# SCH_555_Timer_Based_Keyboard_2023-12-17.net
KiCad netlist of a schematic drawn in EasyEDA
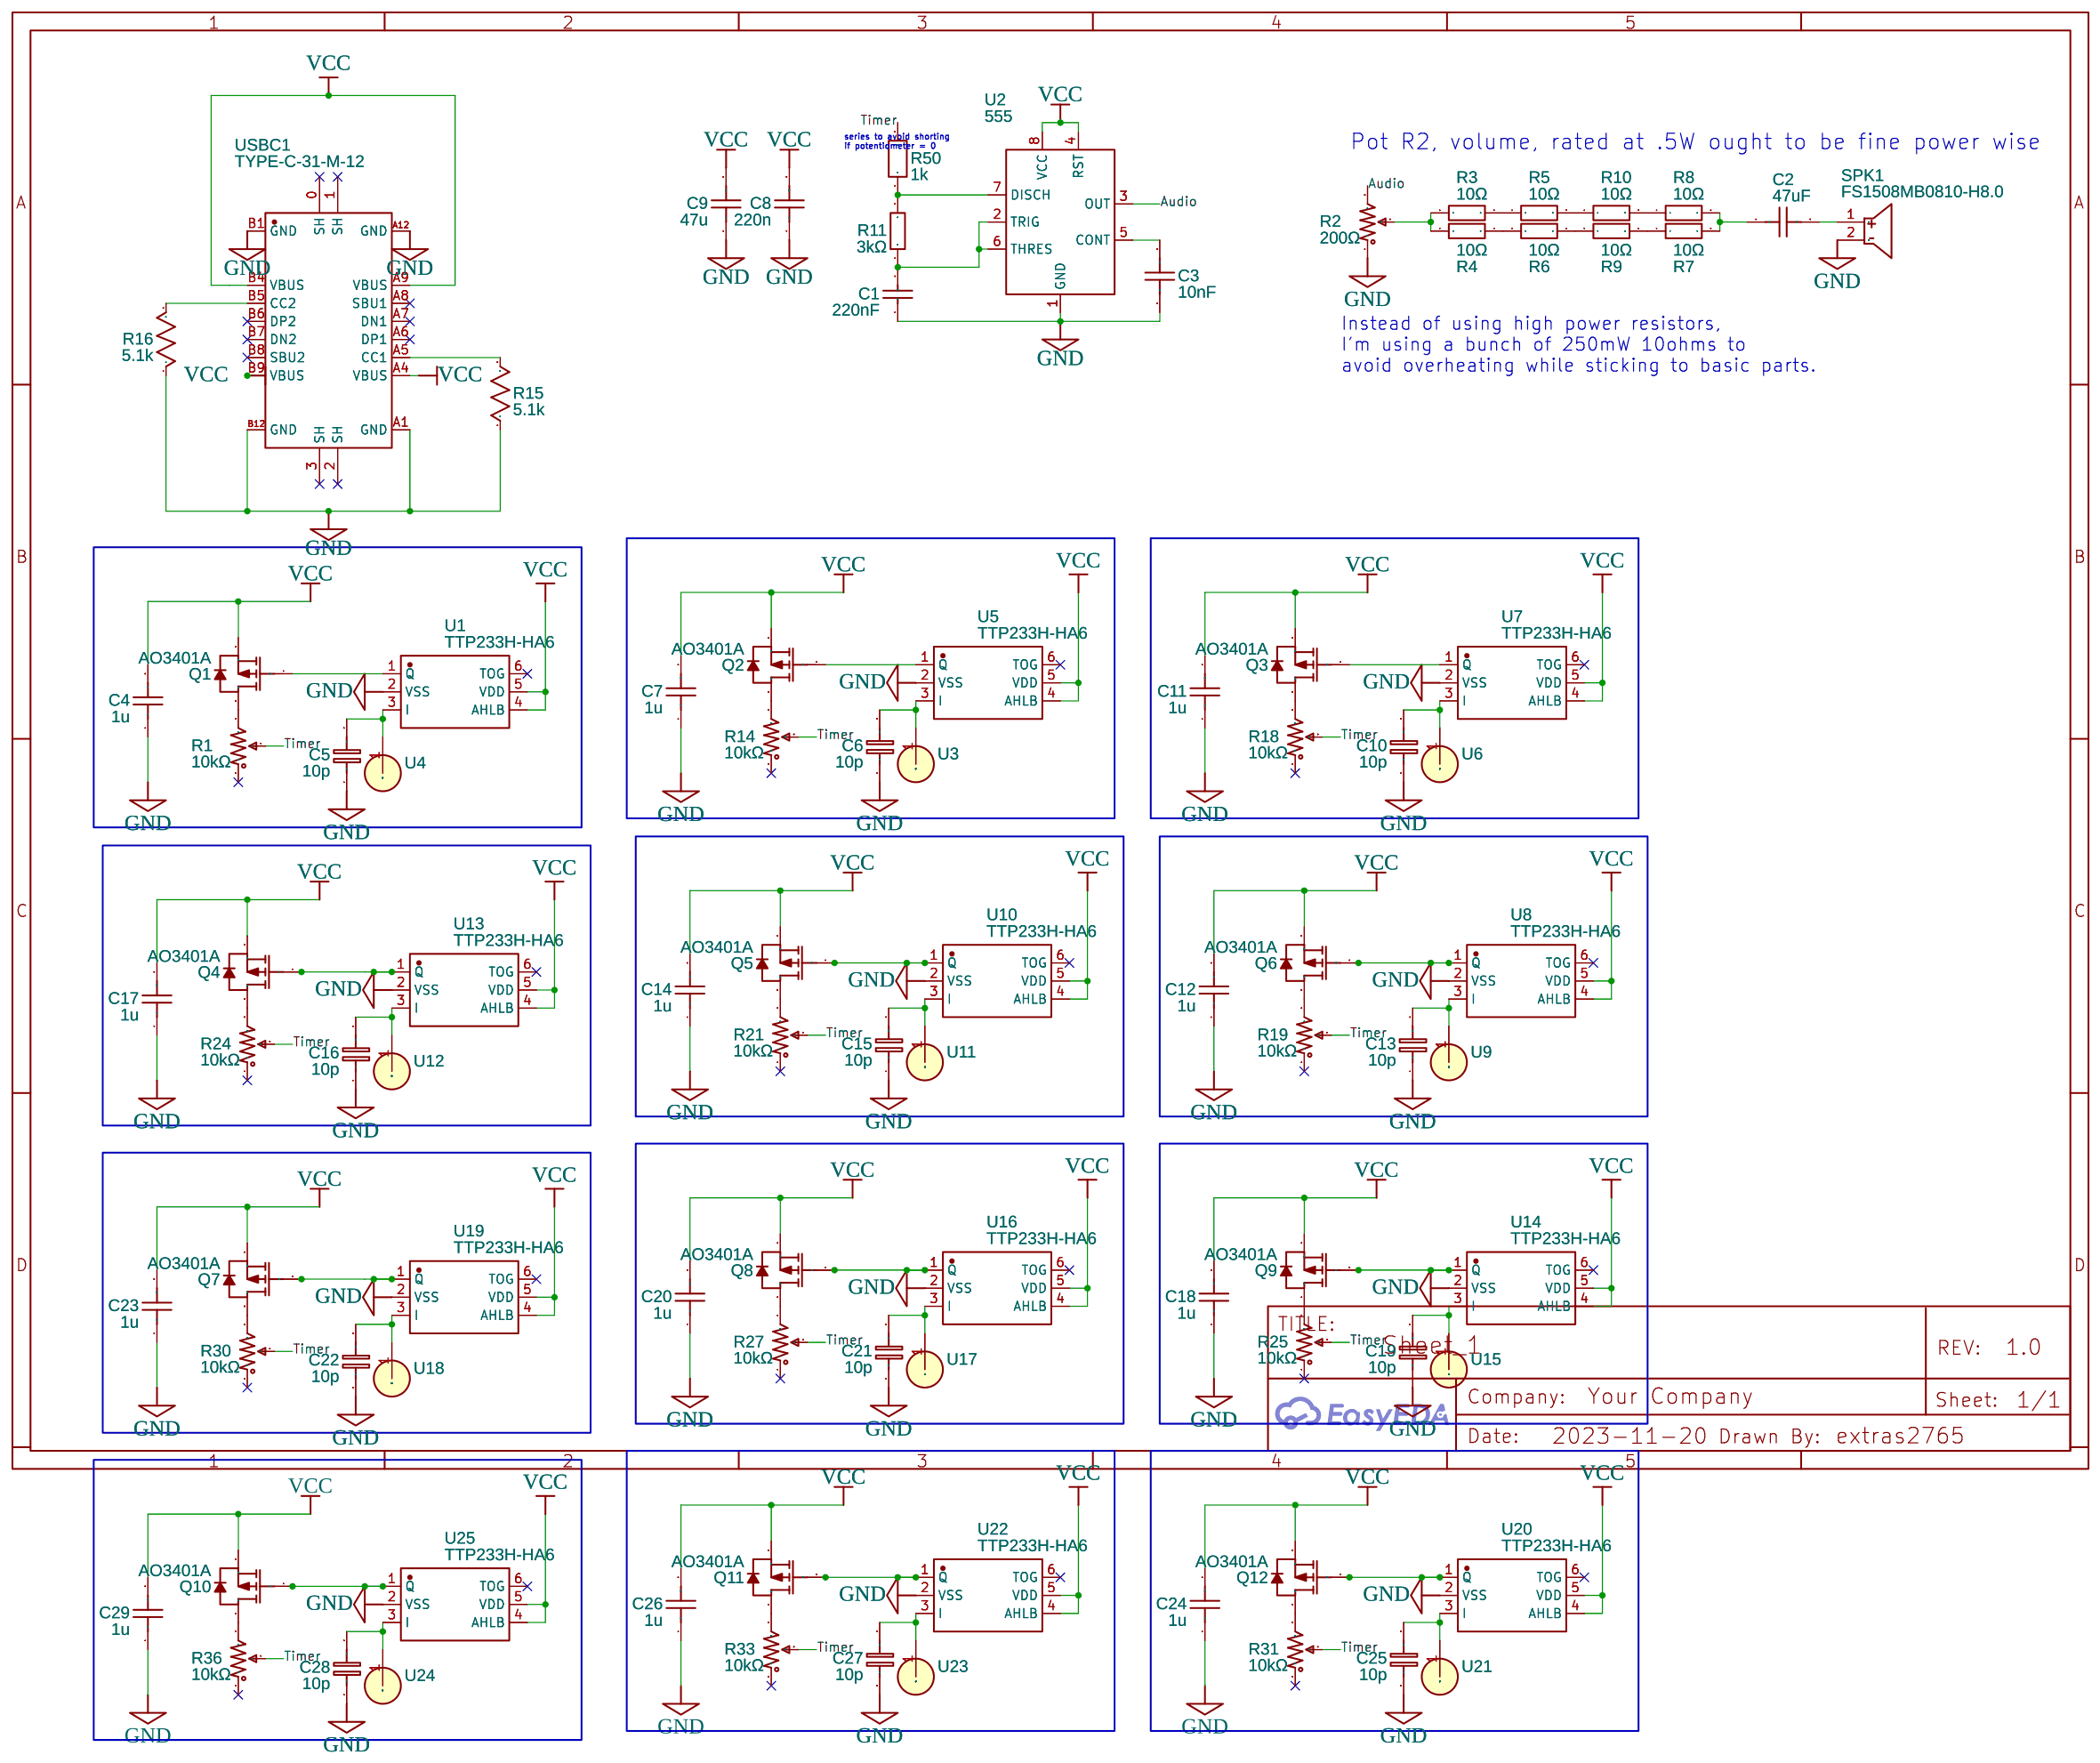
[diagram p0: schematic sheet]

(export (version "E")
  (design (tool "Eeschema 10.0.6"))
  (components
    (comp (ref "C1")
      (value "220nF")
      (fields
        (field (name "Manufacturer Part") "CL21B224KBFNNNE")
        (field (name "Manufacturer") "SAMSUNG(三星)")
      )
      (libsource (lib "") (part "CL21B224KBFNNNE"))
    )
    (comp (ref "C2")
      (value "47uF")
      (fields
        (field (name "Manufacturer Part") "CL31A476MPHNNNE")
        (field (name "Manufacturer") "SAMSUNG(三星)")
      )
      (libsource (lib "") (part "CL31A476MPHNNNE"))
    )
    (comp (ref "C3") (value "10nF") (libsource (lib "") (part "C_0805_US")))
    (comp (ref "C4") (value "1u") (libsource (lib "") (part "C_0805_US_1")))
    (comp (ref "C5") (value "10p") (libsource (lib "") (part "C_0603_EU_1")))
    (comp (ref "C6") (value "10p") (libsource (lib "") (part "C_0603_EU_1")))
    (comp (ref "C7") (value "1u") (libsource (lib "") (part "C_0805_US_1")))
    (comp (ref "C8") (value "220n") (libsource (lib "") (part "C_0805_US_1")))
    (comp (ref "C9") (value "47u") (libsource (lib "") (part "C_0805_US_1")))
    (comp (ref "C10") (value "10p") (libsource (lib "") (part "C_0603_EU_2")))
    (comp (ref "C11") (value "1u") (libsource (lib "") (part "C_0805_US_1")))
    (comp (ref "C12") (value "1u") (libsource (lib "") (part "C_0805_US_1")))
    (comp (ref "C13") (value "10p") (libsource (lib "") (part "C_0603_EU_2")))
    (comp (ref "C14") (value "1u") (libsource (lib "") (part "C_0805_US_1")))
    (comp (ref "C15") (value "10p") (libsource (lib "") (part "C_0603_EU_1")))
    (comp (ref "C16") (value "10p") (libsource (lib "") (part "C_0603_EU_1")))
    (comp (ref "C17") (value "1u") (libsource (lib "") (part "C_0805_US_1")))
    (comp (ref "C18") (value "1u") (libsource (lib "") (part "C_0805_US_1")))
    (comp (ref "C19") (value "10p") (libsource (lib "") (part "C_0603_EU_3")))
    (comp (ref "C20") (value "1u") (libsource (lib "") (part "C_0805_US_1")))
    (comp (ref "C21") (value "10p") (libsource (lib "") (part "C_0603_EU")))
    (comp (ref "C22") (value "10p") (libsource (lib "") (part "C_0603_EU")))
    (comp (ref "C23") (value "1u") (libsource (lib "") (part "C_0805_US_1")))
    (comp (ref "C24") (value "1u") (libsource (lib "") (part "C_0805_US_1")))
    (comp (ref "C25") (value "10p") (libsource (lib "") (part "C_0603_EU_3")))
    (comp (ref "C26") (value "1u") (libsource (lib "") (part "C_0805_US_1")))
    (comp (ref "C27") (value "10p") (libsource (lib "") (part "C_0603_EU")))
    (comp (ref "C28") (value "10p") (libsource (lib "") (part "C_0603_EU")))
    (comp (ref "C29") (value "1u") (libsource (lib "") (part "C_0805_US_1")))
    (comp (ref "Q1")
      (value "AO3401A")
      (fields (field (name "Manufacturer") "AOS"))
      (libsource (lib "") (part "AO3401A"))
    )
    (comp (ref "Q2")
      (value "AO3401A")
      (fields (field (name "Manufacturer") "AOS"))
      (libsource (lib "") (part "AO3401A"))
    )
    (comp (ref "Q3")
      (value "AO3401A")
      (fields (field (name "Manufacturer") "AOS"))
      (libsource (lib "") (part "AO3401A"))
    )
    (comp (ref "Q4")
      (value "AO3401A")
      (fields (field (name "Manufacturer") "AOS"))
      (libsource (lib "") (part "AO3401A"))
    )
    (comp (ref "Q5")
      (value "AO3401A")
      (fields (field (name "Manufacturer") "AOS"))
      (libsource (lib "") (part "AO3401A"))
    )
    (comp (ref "Q6")
      (value "AO3401A")
      (fields (field (name "Manufacturer") "AOS"))
      (libsource (lib "") (part "AO3401A"))
    )
    (comp (ref "Q7")
      (value "AO3401A")
      (fields (field (name "Manufacturer") "AOS"))
      (libsource (lib "") (part "AO3401A"))
    )
    (comp (ref "Q8")
      (value "AO3401A")
      (fields (field (name "Manufacturer") "AOS"))
      (libsource (lib "") (part "AO3401A"))
    )
    (comp (ref "Q9")
      (value "AO3401A")
      (fields (field (name "Manufacturer") "AOS"))
      (libsource (lib "") (part "AO3401A"))
    )
    (comp (ref "Q10")
      (value "AO3401A")
      (fields (field (name "Manufacturer") "AOS"))
      (libsource (lib "") (part "AO3401A"))
    )
    (comp (ref "Q11")
      (value "AO3401A")
      (fields (field (name "Manufacturer") "AOS"))
      (libsource (lib "") (part "AO3401A"))
    )
    (comp (ref "Q12")
      (value "AO3401A")
      (fields (field (name "Manufacturer") "AOS"))
      (libsource (lib "") (part "AO3401A"))
    )
    (comp (ref "R1")
      (value "10kΩ")
      (fields (field (name "Manufacturer Part") "3296W-1-103") (field (name "Manufacturer") "BOCHEN(博晨)"))
      (libsource (lib "") (part "3296W-1-103"))
    )
    (comp (ref "R2")
      (value "200Ω")
      (fields (field (name "Manufacturer Part") "3386P-1-201TLF") (field (name "Manufacturer") "BOURNS"))
      (libsource (lib "") (part "3386P-1-201TLF"))
    )
    (comp (ref "R3")
      (value "10Ω")
      (fields
        (field (name "Manufacturer Part") "1206W4F100JT5E")
        (field (name "Manufacturer") "UNI-ROYAL(厚声)")
      )
      (libsource (lib "") (part "1206W4F100JT5E"))
    )
    (comp (ref "R4")
      (value "10Ω")
      (fields
        (field (name "Manufacturer Part") "1206W4F100JT5E")
        (field (name "Manufacturer") "UNI-ROYAL(厚声)")
      )
      (libsource (lib "") (part "1206W4F100JT5E"))
    )
    (comp (ref "R5")
      (value "10Ω")
      (fields
        (field (name "Manufacturer Part") "1206W4F100JT5E")
        (field (name "Manufacturer") "UNI-ROYAL(厚声)")
      )
      (libsource (lib "") (part "1206W4F100JT5E"))
    )
    (comp (ref "R6")
      (value "10Ω")
      (fields
        (field (name "Manufacturer Part") "1206W4F100JT5E")
        (field (name "Manufacturer") "UNI-ROYAL(厚声)")
      )
      (libsource (lib "") (part "1206W4F100JT5E"))
    )
    (comp (ref "R7")
      (value "10Ω")
      (fields
        (field (name "Manufacturer Part") "1206W4F100JT5E")
        (field (name "Manufacturer") "UNI-ROYAL(厚声)")
      )
      (libsource (lib "") (part "1206W4F100JT5E"))
    )
    (comp (ref "R8")
      (value "10Ω")
      (fields
        (field (name "Manufacturer Part") "1206W4F100JT5E")
        (field (name "Manufacturer") "UNI-ROYAL(厚声)")
      )
      (libsource (lib "") (part "1206W4F100JT5E"))
    )
    (comp (ref "R9")
      (value "10Ω")
      (fields
        (field (name "Manufacturer Part") "1206W4F100JT5E")
        (field (name "Manufacturer") "UNI-ROYAL(厚声)")
      )
      (libsource (lib "") (part "1206W4F100JT5E"))
    )
    (comp (ref "R10")
      (value "10Ω")
      (fields
        (field (name "Manufacturer Part") "1206W4F100JT5E")
        (field (name "Manufacturer") "UNI-ROYAL(厚声)")
      )
      (libsource (lib "") (part "1206W4F100JT5E"))
    )
    (comp (ref "R11")
      (value "3kΩ")
      (fields
        (field (name "Manufacturer Part") "0805W8F3001T5E")
        (field (name "Manufacturer") "UNI-ROYAL(厚声)")
      )
      (libsource (lib "") (part "0805W8F3001T5E"))
    )
    (comp (ref "R14")
      (value "10kΩ")
      (fields (field (name "Manufacturer Part") "3296W-1-103") (field (name "Manufacturer") "BOCHEN(博晨)"))
      (libsource (lib "") (part "3296W-1-103"))
    )
    (comp (ref "R15") (value "5.1k") (libsource (lib "") (part "R_0805_US_1")))
    (comp (ref "R16") (value "5.1k") (libsource (lib "") (part "R_0805_US")))
    (comp (ref "R18")
      (value "10kΩ")
      (fields (field (name "Manufacturer Part") "3296W-1-103") (field (name "Manufacturer") "BOCHEN(博晨)"))
      (libsource (lib "") (part "3296W-1-103"))
    )
    (comp (ref "R19")
      (value "10kΩ")
      (fields (field (name "Manufacturer Part") "3296W-1-103") (field (name "Manufacturer") "BOCHEN(博晨)"))
      (libsource (lib "") (part "3296W-1-103"))
    )
    (comp (ref "R21")
      (value "10kΩ")
      (fields (field (name "Manufacturer Part") "3296W-1-103") (field (name "Manufacturer") "BOCHEN(博晨)"))
      (libsource (lib "") (part "3296W-1-103"))
    )
    (comp (ref "R24")
      (value "10kΩ")
      (fields (field (name "Manufacturer Part") "3296W-1-103") (field (name "Manufacturer") "BOCHEN(博晨)"))
      (libsource (lib "") (part "3296W-1-103"))
    )
    (comp (ref "R25")
      (value "10kΩ")
      (fields (field (name "Manufacturer Part") "3296W-1-103") (field (name "Manufacturer") "BOCHEN(博晨)"))
      (libsource (lib "") (part "3296W-1-103"))
    )
    (comp (ref "R27")
      (value "10kΩ")
      (fields (field (name "Manufacturer Part") "3296W-1-103") (field (name "Manufacturer") "BOCHEN(博晨)"))
      (libsource (lib "") (part "3296W-1-103"))
    )
    (comp (ref "R30")
      (value "10kΩ")
      (fields (field (name "Manufacturer Part") "3296W-1-103") (field (name "Manufacturer") "BOCHEN(博晨)"))
      (libsource (lib "") (part "3296W-1-103"))
    )
    (comp (ref "R31")
      (value "10kΩ")
      (fields (field (name "Manufacturer Part") "3296W-1-103") (field (name "Manufacturer") "BOCHEN(博晨)"))
      (libsource (lib "") (part "3296W-1-103"))
    )
    (comp (ref "R33")
      (value "10kΩ")
      (fields (field (name "Manufacturer Part") "3296W-1-103") (field (name "Manufacturer") "BOCHEN(博晨)"))
      (libsource (lib "") (part "3296W-1-103"))
    )
    (comp (ref "R36")
      (value "10kΩ")
      (fields (field (name "Manufacturer Part") "3296W-1-103") (field (name "Manufacturer") "BOCHEN(博晨)"))
      (libsource (lib "") (part "3296W-1-103"))
    )
    (comp (ref "R50") (value "1k") (libsource (lib "") (part "R_0805_EU")))
    (comp (ref "SPK1")
      (value "FS1508MB0810-H8.0")
      (fields (field (name "Manufacturer") "FUET(福声科技)"))
      (libsource (lib "") (part "FS1508MB0810-H8.0"))
    )
    (comp (ref "U1")
      (value "TTP233H-HA6")
      (fields (field (name "Manufacturer") "TONTEK(通泰)"))
      (libsource (lib "") (part "TTP233H-HA6"))
    )
    (comp (ref "U2")
      (value "555")
      (fields (field (name "Manufacturer Part") "NE555DR") (field (name "Manufacturer") "TI(德州仪器)"))
      (libsource (lib "") (part "NE555DR"))
    )
    (comp (ref "U3") (value "TouchPad") (libsource (lib "") (part "TouchPad")))
    (comp (ref "U4") (value "TouchPad") (libsource (lib "") (part "TouchPad")))
    (comp (ref "U5")
      (value "TTP233H-HA6")
      (fields (field (name "Manufacturer") "TONTEK(通泰)"))
      (libsource (lib "") (part "TTP233H-HA6"))
    )
    (comp (ref "U6") (value "TouchPad") (libsource (lib "") (part "TouchPad")))
    (comp (ref "U7")
      (value "TTP233H-HA6")
      (fields (field (name "Manufacturer") "TONTEK(通泰)"))
      (libsource (lib "") (part "TTP233H-HA6"))
    )
    (comp (ref "U8")
      (value "TTP233H-HA6")
      (fields (field (name "Manufacturer") "TONTEK(通泰)"))
      (libsource (lib "") (part "TTP233H-HA6"))
    )
    (comp (ref "U9") (value "TouchPad") (libsource (lib "") (part "TouchPad")))
    (comp (ref "U10")
      (value "TTP233H-HA6")
      (fields (field (name "Manufacturer") "TONTEK(通泰)"))
      (libsource (lib "") (part "TTP233H-HA6"))
    )
    (comp (ref "U11") (value "TouchPad") (libsource (lib "") (part "TouchPad")))
    (comp (ref "U12") (value "TouchPad") (libsource (lib "") (part "TouchPad")))
    (comp (ref "U13")
      (value "TTP233H-HA6")
      (fields (field (name "Manufacturer") "TONTEK(通泰)"))
      (libsource (lib "") (part "TTP233H-HA6"))
    )
    (comp (ref "U14")
      (value "TTP233H-HA6")
      (fields (field (name "Manufacturer") "TONTEK(通泰)"))
      (libsource (lib "") (part "TTP233H-HA6"))
    )
    (comp (ref "U15") (value "TouchPad") (libsource (lib "") (part "TouchPad")))
    (comp (ref "U16")
      (value "TTP233H-HA6")
      (fields (field (name "Manufacturer") "TONTEK(通泰)"))
      (libsource (lib "") (part "TTP233H-HA6"))
    )
    (comp (ref "U17") (value "TouchPad") (libsource (lib "") (part "TouchPad")))
    (comp (ref "U18") (value "TouchPad") (libsource (lib "") (part "TouchPad")))
    (comp (ref "U19")
      (value "TTP233H-HA6")
      (fields (field (name "Manufacturer") "TONTEK(通泰)"))
      (libsource (lib "") (part "TTP233H-HA6"))
    )
    (comp (ref "U20")
      (value "TTP233H-HA6")
      (fields (field (name "Manufacturer") "TONTEK(通泰)"))
      (libsource (lib "") (part "TTP233H-HA6"))
    )
    (comp (ref "U21") (value "TouchPad") (libsource (lib "") (part "TouchPad")))
    (comp (ref "U22")
      (value "TTP233H-HA6")
      (fields (field (name "Manufacturer") "TONTEK(通泰)"))
      (libsource (lib "") (part "TTP233H-HA6"))
    )
    (comp (ref "U23") (value "TouchPad") (libsource (lib "") (part "TouchPad")))
    (comp (ref "U24") (value "TouchPad") (libsource (lib "") (part "TouchPad")))
    (comp (ref "U25")
      (value "TTP233H-HA6")
      (fields (field (name "Manufacturer") "TONTEK(通泰)"))
      (libsource (lib "") (part "TTP233H-HA6"))
    )
    (comp (ref "USBC1")
      (value "TYPE-C-31-M-12")
      (fields (field (name "Manufacturer") "韩国韩荣"))
      (libsource (lib "") (part "TYPE-C-31-M-12"))
    )
  )
  (nets
    (net (code "1") (name "/Audio") (class "Default")
      (node (ref "R2") (pin "3") (pinfunction "3_3") (pintype "unspecified"))
      (node (ref "U2") (pin "3") (pinfunction "OUT_3") (pintype "unspecified"))
    )
    (net (code "2") (name "/Timer") (class "Default")
      (node (ref "R1") (pin "2") (pinfunction "2_2") (pintype "unspecified"))
      (node (ref "R14") (pin "2") (pinfunction "2_2") (pintype "unspecified"))
      (node (ref "R18") (pin "2") (pinfunction "2_2") (pintype "unspecified"))
      (node (ref "R19") (pin "2") (pinfunction "2_2") (pintype "unspecified"))
      (node (ref "R21") (pin "2") (pinfunction "2_2") (pintype "unspecified"))
      (node (ref "R24") (pin "2") (pinfunction "2_2") (pintype "unspecified"))
      (node (ref "R25") (pin "2") (pinfunction "2_2") (pintype "unspecified"))
      (node (ref "R27") (pin "2") (pinfunction "2_2") (pintype "unspecified"))
      (node (ref "R30") (pin "2") (pinfunction "2_2") (pintype "unspecified"))
      (node (ref "R31") (pin "2") (pinfunction "2_2") (pintype "unspecified"))
      (node (ref "R33") (pin "2") (pinfunction "2_2") (pintype "unspecified"))
      (node (ref "R36") (pin "2") (pinfunction "2_2") (pintype "unspecified"))
      (node (ref "R50") (pin "2") (pinfunction "2_2") (pintype "unspecified"))
    )
    (net (code "3") (name "GND") (class "Default")
      (node (ref "C1") (pin "1") (pinfunction "1_1") (pintype "input"))
      (node (ref "C10") (pin "1") (pinfunction "1_1") (pintype "unspecified"))
      (node (ref "C11") (pin "1") (pinfunction "1_1") (pintype "unspecified"))
      (node (ref "C12") (pin "1") (pinfunction "1_1") (pintype "unspecified"))
      (node (ref "C13") (pin "1") (pinfunction "1_1") (pintype "unspecified"))
      (node (ref "C14") (pin "1") (pinfunction "1_1") (pintype "unspecified"))
      (node (ref "C15") (pin "1") (pinfunction "1_1") (pintype "unspecified"))
      (node (ref "C16") (pin "1") (pinfunction "1_1") (pintype "unspecified"))
      (node (ref "C17") (pin "1") (pinfunction "1_1") (pintype "unspecified"))
      (node (ref "C18") (pin "1") (pinfunction "1_1") (pintype "unspecified"))
      (node (ref "C19") (pin "1") (pinfunction "1_1") (pintype "unspecified"))
      (node (ref "C20") (pin "1") (pinfunction "1_1") (pintype "unspecified"))
      (node (ref "C21") (pin "1") (pinfunction "1_1") (pintype "unspecified"))
      (node (ref "C22") (pin "1") (pinfunction "1_1") (pintype "unspecified"))
      (node (ref "C23") (pin "1") (pinfunction "1_1") (pintype "unspecified"))
      (node (ref "C24") (pin "1") (pinfunction "1_1") (pintype "unspecified"))
      (node (ref "C25") (pin "1") (pinfunction "1_1") (pintype "unspecified"))
      (node (ref "C26") (pin "1") (pinfunction "1_1") (pintype "unspecified"))
      (node (ref "C27") (pin "1") (pinfunction "1_1") (pintype "unspecified"))
      (node (ref "C28") (pin "1") (pinfunction "1_1") (pintype "unspecified"))
      (node (ref "C29") (pin "1") (pinfunction "1_1") (pintype "unspecified"))
      (node (ref "C3") (pin "1") (pinfunction "1_1") (pintype "unspecified"))
      (node (ref "C4") (pin "1") (pinfunction "1_1") (pintype "unspecified"))
      (node (ref "C5") (pin "1") (pinfunction "1_1") (pintype "unspecified"))
      (node (ref "C6") (pin "1") (pinfunction "1_1") (pintype "unspecified"))
      (node (ref "C7") (pin "1") (pinfunction "1_1") (pintype "unspecified"))
      (node (ref "C8") (pin "1") (pinfunction "1_1") (pintype "unspecified"))
      (node (ref "C9") (pin "1") (pinfunction "1_1") (pintype "unspecified"))
      (node (ref "R15") (pin "1") (pinfunction "1_1") (pintype "unspecified"))
      (node (ref "R16") (pin "1") (pinfunction "1_1") (pintype "unspecified"))
      (node (ref "R2") (pin "1") (pinfunction "1_1") (pintype "unspecified"))
      (node (ref "SPK1") (pin "2") (pinfunction "2_2") (pintype "unspecified"))
      (node (ref "U1") (pin "2") (pinfunction "VSS_2") (pintype "unspecified"))
      (node (ref "U10") (pin "2") (pinfunction "VSS_2") (pintype "unspecified"))
      (node (ref "U13") (pin "2") (pinfunction "VSS_2") (pintype "unspecified"))
      (node (ref "U14") (pin "2") (pinfunction "VSS_2") (pintype "unspecified"))
      (node (ref "U16") (pin "2") (pinfunction "VSS_2") (pintype "unspecified"))
      (node (ref "U19") (pin "2") (pinfunction "VSS_2") (pintype "unspecified"))
      (node (ref "U2") (pin "1") (pinfunction "GND_1") (pintype "unspecified"))
      (node (ref "U20") (pin "2") (pinfunction "VSS_2") (pintype "unspecified"))
      (node (ref "U22") (pin "2") (pinfunction "VSS_2") (pintype "unspecified"))
      (node (ref "U25") (pin "2") (pinfunction "VSS_2") (pintype "unspecified"))
      (node (ref "U5") (pin "2") (pinfunction "VSS_2") (pintype "unspecified"))
      (node (ref "U7") (pin "2") (pinfunction "VSS_2") (pintype "unspecified"))
      (node (ref "U8") (pin "2") (pinfunction "VSS_2") (pintype "unspecified"))
      (node (ref "USBC1") (pin "A1") (pinfunction "GND_A1") (pintype "unspecified"))
      (node (ref "USBC1") (pin "A12") (pinfunction "GND_A12") (pintype "unspecified"))
      (node (ref "USBC1") (pin "B1") (pinfunction "GND_B1") (pintype "unspecified"))
      (node (ref "USBC1") (pin "B12") (pinfunction "GND_B12") (pintype "unspecified"))
    )
    (net (code "4") (name "Net-(C2-Pad1)") (class "Default")
      (node (ref "C2") (pin "1") (pinfunction "1_1") (pintype "unspecified"))
      (node (ref "R7") (pin "2") (pinfunction "2_2") (pintype "input"))
      (node (ref "R8") (pin "2") (pinfunction "2_2") (pintype "input"))
    )
    (net (code "5") (name "Net-(C2-Pad2)") (class "Default")
      (node (ref "C2") (pin "2") (pinfunction "2_2") (pintype "unspecified"))
      (node (ref "SPK1") (pin "1") (pinfunction "1_1") (pintype "unspecified"))
    )
    (net (code "6") (name "Net-(Q1-D)") (class "Default")
      (node (ref "Q1") (pin "3") (pinfunction "D_3") (pintype "unspecified"))
      (node (ref "R1") (pin "3") (pinfunction "3_3") (pintype "unspecified"))
    )
    (net (code "7") (name "Net-(Q1-G)") (class "Default")
      (node (ref "Q1") (pin "1") (pinfunction "G_1") (pintype "unspecified"))
      (node (ref "U1") (pin "1") (pinfunction "Q_1") (pintype "unspecified"))
    )
    (net (code "8") (name "Net-(Q2-D)") (class "Default")
      (node (ref "Q2") (pin "3") (pinfunction "D_3") (pintype "unspecified"))
      (node (ref "R14") (pin "3") (pinfunction "3_3") (pintype "unspecified"))
    )
    (net (code "9") (name "Net-(Q2-G)") (class "Default")
      (node (ref "Q2") (pin "1") (pinfunction "G_1") (pintype "unspecified"))
      (node (ref "U5") (pin "1") (pinfunction "Q_1") (pintype "unspecified"))
    )
    (net (code "10") (name "Net-(Q3-D)") (class "Default")
      (node (ref "Q3") (pin "3") (pinfunction "D_3") (pintype "unspecified"))
      (node (ref "R18") (pin "3") (pinfunction "3_3") (pintype "unspecified"))
    )
    (net (code "11") (name "Net-(Q3-G)") (class "Default")
      (node (ref "Q3") (pin "1") (pinfunction "G_1") (pintype "unspecified"))
      (node (ref "U7") (pin "1") (pinfunction "Q_1") (pintype "unspecified"))
    )
    (net (code "12") (name "Net-(Q4-D)") (class "Default")
      (node (ref "Q4") (pin "3") (pinfunction "D_3") (pintype "unspecified"))
      (node (ref "R24") (pin "3") (pinfunction "3_3") (pintype "unspecified"))
    )
    (net (code "13") (name "Net-(Q4-G)") (class "Default")
      (node (ref "Q4") (pin "1") (pinfunction "G_1") (pintype "unspecified"))
      (node (ref "U13") (pin "1") (pinfunction "Q_1") (pintype "unspecified"))
    )
    (net (code "14") (name "Net-(Q5-D)") (class "Default")
      (node (ref "Q5") (pin "3") (pinfunction "D_3") (pintype "unspecified"))
      (node (ref "R21") (pin "3") (pinfunction "3_3") (pintype "unspecified"))
    )
    (net (code "15") (name "Net-(Q5-G)") (class "Default")
      (node (ref "Q5") (pin "1") (pinfunction "G_1") (pintype "unspecified"))
      (node (ref "U10") (pin "1") (pinfunction "Q_1") (pintype "unspecified"))
    )
    (net (code "16") (name "Net-(Q6-D)") (class "Default")
      (node (ref "Q6") (pin "3") (pinfunction "D_3") (pintype "unspecified"))
      (node (ref "R19") (pin "3") (pinfunction "3_3") (pintype "unspecified"))
    )
    (net (code "17") (name "Net-(Q6-G)") (class "Default")
      (node (ref "Q6") (pin "1") (pinfunction "G_1") (pintype "unspecified"))
      (node (ref "U8") (pin "1") (pinfunction "Q_1") (pintype "unspecified"))
    )
    (net (code "18") (name "Net-(Q7-D)") (class "Default")
      (node (ref "Q7") (pin "3") (pinfunction "D_3") (pintype "unspecified"))
      (node (ref "R30") (pin "3") (pinfunction "3_3") (pintype "unspecified"))
    )
    (net (code "19") (name "Net-(Q7-G)") (class "Default")
      (node (ref "Q7") (pin "1") (pinfunction "G_1") (pintype "unspecified"))
      (node (ref "U19") (pin "1") (pinfunction "Q_1") (pintype "unspecified"))
    )
    (net (code "20") (name "Net-(Q8-D)") (class "Default")
      (node (ref "Q8") (pin "3") (pinfunction "D_3") (pintype "unspecified"))
      (node (ref "R27") (pin "3") (pinfunction "3_3") (pintype "unspecified"))
    )
    (net (code "21") (name "Net-(Q8-G)") (class "Default")
      (node (ref "Q8") (pin "1") (pinfunction "G_1") (pintype "unspecified"))
      (node (ref "U16") (pin "1") (pinfunction "Q_1") (pintype "unspecified"))
    )
    (net (code "22") (name "Net-(Q9-D)") (class "Default")
      (node (ref "Q9") (pin "3") (pinfunction "D_3") (pintype "unspecified"))
      (node (ref "R25") (pin "3") (pinfunction "3_3") (pintype "unspecified"))
    )
    (net (code "23") (name "Net-(Q9-G)") (class "Default")
      (node (ref "Q9") (pin "1") (pinfunction "G_1") (pintype "unspecified"))
      (node (ref "U14") (pin "1") (pinfunction "Q_1") (pintype "unspecified"))
    )
    (net (code "24") (name "Net-(Q10-D)") (class "Default")
      (node (ref "Q10") (pin "3") (pinfunction "D_3") (pintype "unspecified"))
      (node (ref "R36") (pin "3") (pinfunction "3_3") (pintype "unspecified"))
    )
    (net (code "25") (name "Net-(Q10-G)") (class "Default")
      (node (ref "Q10") (pin "1") (pinfunction "G_1") (pintype "unspecified"))
      (node (ref "U25") (pin "1") (pinfunction "Q_1") (pintype "unspecified"))
    )
    (net (code "26") (name "Net-(Q11-D)") (class "Default")
      (node (ref "Q11") (pin "3") (pinfunction "D_3") (pintype "unspecified"))
      (node (ref "R33") (pin "3") (pinfunction "3_3") (pintype "unspecified"))
    )
    (net (code "27") (name "Net-(Q11-G)") (class "Default")
      (node (ref "Q11") (pin "1") (pinfunction "G_1") (pintype "unspecified"))
      (node (ref "U22") (pin "1") (pinfunction "Q_1") (pintype "unspecified"))
    )
    (net (code "28") (name "Net-(Q12-D)") (class "Default")
      (node (ref "Q12") (pin "3") (pinfunction "D_3") (pintype "unspecified"))
      (node (ref "R31") (pin "3") (pinfunction "3_3") (pintype "unspecified"))
    )
    (net (code "29") (name "Net-(Q12-G)") (class "Default")
      (node (ref "Q12") (pin "1") (pinfunction "G_1") (pintype "unspecified"))
      (node (ref "U20") (pin "1") (pinfunction "Q_1") (pintype "unspecified"))
    )
    (net (code "30") (name "Net-(R2-Pad2)") (class "Default")
      (node (ref "R2") (pin "2") (pinfunction "2_2") (pintype "unspecified"))
      (node (ref "R3") (pin "1") (pinfunction "1_1") (pintype "input"))
      (node (ref "R4") (pin "1") (pinfunction "1_1") (pintype "input"))
    )
    (net (code "31") (name "Net-(R3-Pad2)") (class "Default")
      (node (ref "R3") (pin "2") (pinfunction "2_2") (pintype "input"))
      (node (ref "R5") (pin "1") (pinfunction "1_1") (pintype "input"))
    )
    (net (code "32") (name "Net-(R4-Pad2)") (class "Default")
      (node (ref "R4") (pin "2") (pinfunction "2_2") (pintype "input"))
      (node (ref "R6") (pin "1") (pinfunction "1_1") (pintype "input"))
    )
    (net (code "33") (name "Net-(R6-Pad2)") (class "Default")
      (node (ref "R6") (pin "2") (pinfunction "2_2") (pintype "input"))
      (node (ref "R9") (pin "1") (pinfunction "1_1") (pintype "input"))
    )
    (net (code "34") (name "Net-(R7-Pad1)") (class "Default")
      (node (ref "R7") (pin "1") (pinfunction "1_1") (pintype "input"))
      (node (ref "R9") (pin "2") (pinfunction "2_2") (pintype "input"))
    )
    (net (code "35") (name "Net-(R10-Pad1)") (class "Default")
      (node (ref "R10") (pin "1") (pinfunction "1_1") (pintype "input"))
      (node (ref "R5") (pin "2") (pinfunction "2_2") (pintype "input"))
    )
    (net (code "36") (name "Net-(R10-Pad2)") (class "Default")
      (node (ref "R10") (pin "2") (pinfunction "2_2") (pintype "input"))
      (node (ref "R8") (pin "1") (pinfunction "1_1") (pintype "input"))
    )
    (net (code "37") (name "Net-(U1-I)") (class "Default")
      (node (ref "C5") (pin "2") (pinfunction "2_2") (pintype "unspecified"))
      (node (ref "U1") (pin "3") (pinfunction "I_3") (pintype "unspecified"))
      (node (ref "U4") (pin "1") (pinfunction "Touch_1") (pintype "unspecified"))
    )
    (net (code "38") (name "Net-(U2-CONT)") (class "Default")
      (node (ref "C3") (pin "2") (pinfunction "2_2") (pintype "unspecified"))
      (node (ref "U2") (pin "5") (pinfunction "CONT_5") (pintype "unspecified"))
    )
    (net (code "39") (name "Net-(U2-DISCH)") (class "Default")
      (node (ref "R11") (pin "2") (pinfunction "2_2") (pintype "input"))
      (node (ref "R50") (pin "1") (pinfunction "1_1") (pintype "unspecified"))
      (node (ref "U2") (pin "7") (pinfunction "DISCH_7") (pintype "unspecified"))
    )
    (net (code "40") (name "Net-(U2-THRES)") (class "Default")
      (node (ref "C1") (pin "2") (pinfunction "2_2") (pintype "input"))
      (node (ref "R11") (pin "1") (pinfunction "1_1") (pintype "input"))
      (node (ref "U2") (pin "2") (pinfunction "TRIG_2") (pintype "unspecified"))
      (node (ref "U2") (pin "6") (pinfunction "THRES_6") (pintype "unspecified"))
    )
    (net (code "41") (name "Net-(U3-Touch)") (class "Default")
      (node (ref "C6") (pin "2") (pinfunction "2_2") (pintype "unspecified"))
      (node (ref "U3") (pin "1") (pinfunction "Touch_1") (pintype "unspecified"))
      (node (ref "U5") (pin "3") (pinfunction "I_3") (pintype "unspecified"))
    )
    (net (code "42") (name "Net-(U6-Touch)") (class "Default")
      (node (ref "C10") (pin "2") (pinfunction "2_2") (pintype "unspecified"))
      (node (ref "U6") (pin "1") (pinfunction "Touch_1") (pintype "unspecified"))
      (node (ref "U7") (pin "3") (pinfunction "I_3") (pintype "unspecified"))
    )
    (net (code "43") (name "Net-(U8-I)") (class "Default")
      (node (ref "C13") (pin "2") (pinfunction "2_2") (pintype "unspecified"))
      (node (ref "U8") (pin "3") (pinfunction "I_3") (pintype "unspecified"))
      (node (ref "U9") (pin "1") (pinfunction "Touch_1") (pintype "unspecified"))
    )
    (net (code "44") (name "Net-(U10-I)") (class "Default")
      (node (ref "C15") (pin "2") (pinfunction "2_2") (pintype "unspecified"))
      (node (ref "U10") (pin "3") (pinfunction "I_3") (pintype "unspecified"))
      (node (ref "U11") (pin "1") (pinfunction "Touch_1") (pintype "unspecified"))
    )
    (net (code "45") (name "Net-(U12-Touch)") (class "Default")
      (node (ref "C16") (pin "2") (pinfunction "2_2") (pintype "unspecified"))
      (node (ref "U12") (pin "1") (pinfunction "Touch_1") (pintype "unspecified"))
      (node (ref "U13") (pin "3") (pinfunction "I_3") (pintype "unspecified"))
    )
    (net (code "46") (name "Net-(U14-I)") (class "Default")
      (node (ref "C19") (pin "2") (pinfunction "2_2") (pintype "unspecified"))
      (node (ref "U14") (pin "3") (pinfunction "I_3") (pintype "unspecified"))
      (node (ref "U15") (pin "1") (pinfunction "Touch_1") (pintype "unspecified"))
    )
    (net (code "47") (name "Net-(U16-I)") (class "Default")
      (node (ref "C21") (pin "2") (pinfunction "2_2") (pintype "unspecified"))
      (node (ref "U16") (pin "3") (pinfunction "I_3") (pintype "unspecified"))
      (node (ref "U17") (pin "1") (pinfunction "Touch_1") (pintype "unspecified"))
    )
    (net (code "48") (name "Net-(U18-Touch)") (class "Default")
      (node (ref "C22") (pin "2") (pinfunction "2_2") (pintype "unspecified"))
      (node (ref "U18") (pin "1") (pinfunction "Touch_1") (pintype "unspecified"))
      (node (ref "U19") (pin "3") (pinfunction "I_3") (pintype "unspecified"))
    )
    (net (code "49") (name "Net-(U20-I)") (class "Default")
      (node (ref "C25") (pin "2") (pinfunction "2_2") (pintype "unspecified"))
      (node (ref "U20") (pin "3") (pinfunction "I_3") (pintype "unspecified"))
      (node (ref "U21") (pin "1") (pinfunction "Touch_1") (pintype "unspecified"))
    )
    (net (code "50") (name "Net-(U22-I)") (class "Default")
      (node (ref "C27") (pin "2") (pinfunction "2_2") (pintype "unspecified"))
      (node (ref "U22") (pin "3") (pinfunction "I_3") (pintype "unspecified"))
      (node (ref "U23") (pin "1") (pinfunction "Touch_1") (pintype "unspecified"))
    )
    (net (code "51") (name "Net-(U24-Touch)") (class "Default")
      (node (ref "C28") (pin "2") (pinfunction "2_2") (pintype "unspecified"))
      (node (ref "U24") (pin "1") (pinfunction "Touch_1") (pintype "unspecified"))
      (node (ref "U25") (pin "3") (pinfunction "I_3") (pintype "unspecified"))
    )
    (net (code "52") (name "Net-(USBC1-CC1)") (class "Default")
      (node (ref "R15") (pin "2") (pinfunction "2_2") (pintype "unspecified"))
      (node (ref "USBC1") (pin "A5") (pinfunction "CC1_A5") (pintype "unspecified"))
    )
    (net (code "53") (name "Net-(USBC1-CC2)") (class "Default")
      (node (ref "R16") (pin "2") (pinfunction "2_2") (pintype "unspecified"))
      (node (ref "USBC1") (pin "B5") (pinfunction "CC2_B5") (pintype "unspecified"))
    )
    (net (code "54") (name "VCC") (class "Default")
      (node (ref "C11") (pin "2") (pinfunction "2_2") (pintype "unspecified"))
      (node (ref "C12") (pin "2") (pinfunction "2_2") (pintype "unspecified"))
      (node (ref "C14") (pin "2") (pinfunction "2_2") (pintype "unspecified"))
      (node (ref "C17") (pin "2") (pinfunction "2_2") (pintype "unspecified"))
      (node (ref "C18") (pin "2") (pinfunction "2_2") (pintype "unspecified"))
      (node (ref "C20") (pin "2") (pinfunction "2_2") (pintype "unspecified"))
      (node (ref "C23") (pin "2") (pinfunction "2_2") (pintype "unspecified"))
      (node (ref "C24") (pin "2") (pinfunction "2_2") (pintype "unspecified"))
      (node (ref "C26") (pin "2") (pinfunction "2_2") (pintype "unspecified"))
      (node (ref "C29") (pin "2") (pinfunction "2_2") (pintype "unspecified"))
      (node (ref "C4") (pin "2") (pinfunction "2_2") (pintype "unspecified"))
      (node (ref "C7") (pin "2") (pinfunction "2_2") (pintype "unspecified"))
      (node (ref "C8") (pin "2") (pinfunction "2_2") (pintype "unspecified"))
      (node (ref "C9") (pin "2") (pinfunction "2_2") (pintype "unspecified"))
      (node (ref "Q1") (pin "2") (pinfunction "S_2") (pintype "unspecified"))
      (node (ref "Q10") (pin "2") (pinfunction "S_2") (pintype "unspecified"))
      (node (ref "Q11") (pin "2") (pinfunction "S_2") (pintype "unspecified"))
      (node (ref "Q12") (pin "2") (pinfunction "S_2") (pintype "unspecified"))
      (node (ref "Q2") (pin "2") (pinfunction "S_2") (pintype "unspecified"))
      (node (ref "Q3") (pin "2") (pinfunction "S_2") (pintype "unspecified"))
      (node (ref "Q4") (pin "2") (pinfunction "S_2") (pintype "unspecified"))
      (node (ref "Q5") (pin "2") (pinfunction "S_2") (pintype "unspecified"))
      (node (ref "Q6") (pin "2") (pinfunction "S_2") (pintype "unspecified"))
      (node (ref "Q7") (pin "2") (pinfunction "S_2") (pintype "unspecified"))
      (node (ref "Q8") (pin "2") (pinfunction "S_2") (pintype "unspecified"))
      (node (ref "Q9") (pin "2") (pinfunction "S_2") (pintype "unspecified"))
      (node (ref "U1") (pin "4") (pinfunction "AHLB_4") (pintype "unspecified"))
      (node (ref "U1") (pin "5") (pinfunction "VDD_5") (pintype "unspecified"))
      (node (ref "U10") (pin "4") (pinfunction "AHLB_4") (pintype "unspecified"))
      (node (ref "U10") (pin "5") (pinfunction "VDD_5") (pintype "unspecified"))
      (node (ref "U13") (pin "4") (pinfunction "AHLB_4") (pintype "unspecified"))
      (node (ref "U13") (pin "5") (pinfunction "VDD_5") (pintype "unspecified"))
      (node (ref "U14") (pin "4") (pinfunction "AHLB_4") (pintype "unspecified"))
      (node (ref "U14") (pin "5") (pinfunction "VDD_5") (pintype "unspecified"))
      (node (ref "U16") (pin "4") (pinfunction "AHLB_4") (pintype "unspecified"))
      (node (ref "U16") (pin "5") (pinfunction "VDD_5") (pintype "unspecified"))
      (node (ref "U19") (pin "4") (pinfunction "AHLB_4") (pintype "unspecified"))
      (node (ref "U19") (pin "5") (pinfunction "VDD_5") (pintype "unspecified"))
      (node (ref "U2") (pin "4") (pinfunction "RST_4") (pintype "unspecified"))
      (node (ref "U2") (pin "8") (pinfunction "VCC_8") (pintype "unspecified"))
      (node (ref "U20") (pin "4") (pinfunction "AHLB_4") (pintype "unspecified"))
      (node (ref "U20") (pin "5") (pinfunction "VDD_5") (pintype "unspecified"))
      (node (ref "U22") (pin "4") (pinfunction "AHLB_4") (pintype "unspecified"))
      (node (ref "U22") (pin "5") (pinfunction "VDD_5") (pintype "unspecified"))
      (node (ref "U25") (pin "4") (pinfunction "AHLB_4") (pintype "unspecified"))
      (node (ref "U25") (pin "5") (pinfunction "VDD_5") (pintype "unspecified"))
      (node (ref "U5") (pin "4") (pinfunction "AHLB_4") (pintype "unspecified"))
      (node (ref "U5") (pin "5") (pinfunction "VDD_5") (pintype "unspecified"))
      (node (ref "U7") (pin "4") (pinfunction "AHLB_4") (pintype "unspecified"))
      (node (ref "U7") (pin "5") (pinfunction "VDD_5") (pintype "unspecified"))
      (node (ref "U8") (pin "4") (pinfunction "AHLB_4") (pintype "unspecified"))
      (node (ref "U8") (pin "5") (pinfunction "VDD_5") (pintype "unspecified"))
      (node (ref "USBC1") (pin "A4") (pinfunction "VBUS_A4") (pintype "unspecified"))
      (node (ref "USBC1") (pin "A9") (pinfunction "VBUS_A9") (pintype "unspecified"))
      (node (ref "USBC1") (pin "B4") (pinfunction "VBUS_B4") (pintype "unspecified"))
      (node (ref "USBC1") (pin "B9") (pinfunction "VBUS_B9") (pintype "unspecified"))
    )
    (net (code "55") (name "unconnected-(R1-Pad1)") (class "Default")
      (node (ref "R1") (pin "1") (pinfunction "1_1") (pintype "unspecified+no_connect"))
    )
    (net (code "56") (name "unconnected-(R14-Pad1)") (class "Default")
      (node (ref "R14") (pin "1") (pinfunction "1_1") (pintype "unspecified+no_connect"))
    )
    (net (code "57") (name "unconnected-(R18-Pad1)") (class "Default")
      (node (ref "R18") (pin "1") (pinfunction "1_1") (pintype "unspecified+no_connect"))
    )
    (net (code "58") (name "unconnected-(R19-Pad1)") (class "Default")
      (node (ref "R19") (pin "1") (pinfunction "1_1") (pintype "unspecified+no_connect"))
    )
    (net (code "59") (name "unconnected-(R21-Pad1)") (class "Default")
      (node (ref "R21") (pin "1") (pinfunction "1_1") (pintype "unspecified+no_connect"))
    )
    (net (code "60") (name "unconnected-(R24-Pad1)") (class "Default")
      (node (ref "R24") (pin "1") (pinfunction "1_1") (pintype "unspecified+no_connect"))
    )
    (net (code "61") (name "unconnected-(R25-Pad1)") (class "Default")
      (node (ref "R25") (pin "1") (pinfunction "1_1") (pintype "unspecified+no_connect"))
    )
    (net (code "62") (name "unconnected-(R27-Pad1)") (class "Default")
      (node (ref "R27") (pin "1") (pinfunction "1_1") (pintype "unspecified+no_connect"))
    )
    (net (code "63") (name "unconnected-(R30-Pad1)") (class "Default")
      (node (ref "R30") (pin "1") (pinfunction "1_1") (pintype "unspecified+no_connect"))
    )
    (net (code "64") (name "unconnected-(R31-Pad1)") (class "Default")
      (node (ref "R31") (pin "1") (pinfunction "1_1") (pintype "unspecified+no_connect"))
    )
    (net (code "65") (name "unconnected-(R33-Pad1)") (class "Default")
      (node (ref "R33") (pin "1") (pinfunction "1_1") (pintype "unspecified+no_connect"))
    )
    (net (code "66") (name "unconnected-(R36-Pad1)") (class "Default")
      (node (ref "R36") (pin "1") (pinfunction "1_1") (pintype "unspecified+no_connect"))
    )
    (net (code "67") (name "unconnected-(U1-TOG-Pad6)") (class "Default")
      (node (ref "U1") (pin "6") (pinfunction "TOG_6") (pintype "unspecified+no_connect"))
    )
    (net (code "68") (name "unconnected-(U5-TOG-Pad6)") (class "Default")
      (node (ref "U5") (pin "6") (pinfunction "TOG_6") (pintype "unspecified+no_connect"))
    )
    (net (code "69") (name "unconnected-(U7-TOG-Pad6)") (class "Default")
      (node (ref "U7") (pin "6") (pinfunction "TOG_6") (pintype "unspecified+no_connect"))
    )
    (net (code "70") (name "unconnected-(U8-TOG-Pad6)") (class "Default")
      (node (ref "U8") (pin "6") (pinfunction "TOG_6") (pintype "unspecified+no_connect"))
    )
    (net (code "71") (name "unconnected-(U10-TOG-Pad6)") (class "Default")
      (node (ref "U10") (pin "6") (pinfunction "TOG_6") (pintype "unspecified+no_connect"))
    )
    (net (code "72") (name "unconnected-(U13-TOG-Pad6)") (class "Default")
      (node (ref "U13") (pin "6") (pinfunction "TOG_6") (pintype "unspecified+no_connect"))
    )
    (net (code "73") (name "unconnected-(U14-TOG-Pad6)") (class "Default")
      (node (ref "U14") (pin "6") (pinfunction "TOG_6") (pintype "unspecified+no_connect"))
    )
    (net (code "74") (name "unconnected-(U16-TOG-Pad6)") (class "Default")
      (node (ref "U16") (pin "6") (pinfunction "TOG_6") (pintype "unspecified+no_connect"))
    )
    (net (code "75") (name "unconnected-(U19-TOG-Pad6)") (class "Default")
      (node (ref "U19") (pin "6") (pinfunction "TOG_6") (pintype "unspecified+no_connect"))
    )
    (net (code "76") (name "unconnected-(U20-TOG-Pad6)") (class "Default")
      (node (ref "U20") (pin "6") (pinfunction "TOG_6") (pintype "unspecified+no_connect"))
    )
    (net (code "77") (name "unconnected-(U22-TOG-Pad6)") (class "Default")
      (node (ref "U22") (pin "6") (pinfunction "TOG_6") (pintype "unspecified+no_connect"))
    )
    (net (code "78") (name "unconnected-(U25-TOG-Pad6)") (class "Default")
      (node (ref "U25") (pin "6") (pinfunction "TOG_6") (pintype "unspecified+no_connect"))
    )
    (net (code "79") (name "unconnected-(USBC1-DN1-PadA7)") (class "Default")
      (node (ref "USBC1") (pin "A7") (pinfunction "DN1_A7") (pintype "unspecified+no_connect"))
    )
    (net (code "80") (name "unconnected-(USBC1-DN2-PadB7)") (class "Default")
      (node (ref "USBC1") (pin "B7") (pinfunction "DN2_B7") (pintype "unspecified+no_connect"))
    )
    (net (code "81") (name "unconnected-(USBC1-DP1-PadA6)") (class "Default")
      (node (ref "USBC1") (pin "A6") (pinfunction "DP1_A6") (pintype "unspecified+no_connect"))
    )
    (net (code "82") (name "unconnected-(USBC1-DP2-PadB6)") (class "Default")
      (node (ref "USBC1") (pin "B6") (pinfunction "DP2_B6") (pintype "unspecified+no_connect"))
    )
    (net (code "83") (name "unconnected-(USBC1-SBU1-PadA8)") (class "Default")
      (node (ref "USBC1") (pin "A8") (pinfunction "SBU1_A8") (pintype "unspecified+no_connect"))
    )
    (net (code "84") (name "unconnected-(USBC1-SBU2-PadB8)") (class "Default")
      (node (ref "USBC1") (pin "B8") (pinfunction "SBU2_B8") (pintype "unspecified+no_connect"))
    )
    (net (code "85") (name "unconnected-(USBC1-SH-Pad0)") (class "Default")
      (node (ref "USBC1") (pin "0") (pinfunction "SH_0") (pintype "unspecified+no_connect"))
    )
    (net (code "86") (name "unconnected-(USBC1-SH-Pad1)") (class "Default")
      (node (ref "USBC1") (pin "1") (pinfunction "SH_1") (pintype "unspecified+no_connect"))
    )
    (net (code "87") (name "unconnected-(USBC1-SH-Pad2)") (class "Default")
      (node (ref "USBC1") (pin "2") (pinfunction "SH_2") (pintype "unspecified+no_connect"))
    )
    (net (code "88") (name "unconnected-(USBC1-SH-Pad3)") (class "Default")
      (node (ref "USBC1") (pin "3") (pinfunction "SH_3") (pintype "unspecified+no_connect"))
    )
  )
)
